# 05-Power.net
KiCad netlist of a schematic drawn in Altium Designer
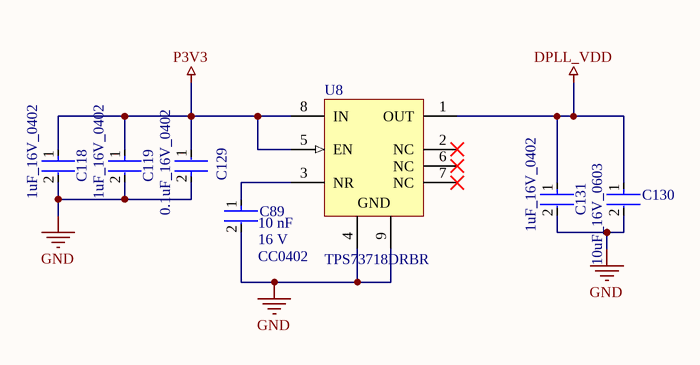
[diagram p0: 05-Power.SchDoc]

(export (version "E")
  (design (tool "Eeschema 10.0.6"))
  (components
    (comp (ref "C89")
      (value "10 nF")
      (footprint "FP-CC0402-MFG")
      (description "CAP CER 10000PF 16V X7R 0402")
      (fields
        (field (name "MANUFACTURER PART NUMBER") "CC0402KRX7R7BB103")
        (field (name "TOLERANCE") "0.1")
        (field (name "PACKAGE") "CC0402")
        (field (name "VOLTAGE RATING") "16 V")
      )
      (libsource (lib "Altium Content Vault") (part "11868f565c42a9108669ba33697ecf6"))
    )
    (comp (ref "C118")
      (value "1uF_16V_0402")
      (footprint "FP-0402-L_1_0_0_05-W_0_5-IPC_C")
      (description "None")
      (fields (field (name "TOLERANCE") "20%") (field (name "VOLTAGE") "16V"))
      (libsource (lib "Altium Content Vault") (part "b4654b650e69147ec39a6b967a45e02"))
    )
    (comp (ref "C119")
      (value "1uF_16V_0402")
      (footprint "FP-0402-L_1_0_0_05-W_0_5-IPC_C")
      (description "None")
      (fields (field (name "TOLERANCE") "20%") (field (name "VOLTAGE") "16V"))
      (libsource (lib "Altium Content Vault") (part "b4654b650e69147ec39a6b967a45e02"))
    )
    (comp (ref "C129")
      (value "0.1uF_16V_0402")
      (footprint "FP-GRM15-MFG")
      (description "CAP CER 0.1UF 16V X7R 0402")
      (fields (field (name "MANUFACTURER PART NUMBER") "GRM155R71C104KA88D") (field (name "TOLERANCE") "10%"))
      (libsource (lib "Altium Content Vault") (part "236180d848d6139a670b325ea6854c9"))
    )
    (comp (ref "C130")
      (value "10uF_16V_0603")
      (footprint "FP-MK107BA-IPC_A")
      (description "None")
      (fields (field (name "TOLERANCE") "20%"))
      (libsource (lib "Altium Content Vault") (part "b4654b650e69147ec39a6b967a45e02"))
    )
    (comp (ref "C131")
      (value "1uF_16V_0402")
      (footprint "FP-0402-L_1_0_0_05-W_0_5-IPC_C")
      (description "None")
      (fields (field (name "TOLERANCE") "20%") (field (name "VOLTAGE") "16V"))
      (libsource (lib "Altium Content Vault") (part "b4654b650e69147ec39a6b967a45e02"))
    )
    (comp (ref "U8")
      (value "TPS73718DRBR")
      (footprint "DRB0008A_V")
      (fields (field (name "MANUFACTURER") "Texas Instruments"))
      (libsource (lib "Altium Content Vault") (part "TI-TPS73718DRB8-1750X1500TP"))
    )
  )
  (nets
    (net (code "1") (name "DPLL_VDD") (class "Default")
      (node (ref "C130") (pin "1") (pinfunction "1_1") (pintype "passive"))
      (node (ref "C131") (pin "1") (pinfunction "1_1") (pintype "passive"))
      (node (ref "U8") (pin "1") (pinfunction "OUT_1") (pintype "power_in"))
    )
    (net (code "2") (name "GND") (class "Default")
      (node (ref "C118") (pin "2") (pinfunction "2_2") (pintype "passive"))
      (node (ref "C119") (pin "2") (pinfunction "2_2") (pintype "passive"))
      (node (ref "C129") (pin "2") (pinfunction "2_2") (pintype "passive"))
      (node (ref "C130") (pin "2") (pinfunction "2_2") (pintype "passive"))
      (node (ref "C131") (pin "2") (pinfunction "2_2") (pintype "passive"))
      (node (ref "C89") (pin "2") (pinfunction "2_2") (pintype "passive"))
      (node (ref "U8") (pin "4") (pinfunction "GND_4") (pintype "power_in"))
      (node (ref "U8") (pin "9") (pinfunction "GND_9") (pintype "power_in"))
    )
    (net (code "3") (name "Net-(U8-NR)") (class "Default")
      (node (ref "C89") (pin "1") (pinfunction "1_1") (pintype "passive"))
      (node (ref "U8") (pin "3") (pinfunction "NR_3") (pintype "passive"))
    )
    (net (code "4") (name "P3V3") (class "Default")
      (node (ref "C118") (pin "1") (pinfunction "1_1") (pintype "passive"))
      (node (ref "C119") (pin "1") (pinfunction "1_1") (pintype "passive"))
      (node (ref "C129") (pin "1") (pinfunction "1_1") (pintype "passive"))
      (node (ref "U8") (pin "5") (pinfunction "EN_5") (pintype "input"))
      (node (ref "U8") (pin "8") (pinfunction "IN_8") (pintype "power_in"))
    )
    (net (code "5") (name "unconnected-(U8-NC-Pad2)") (class "Default")
      (node (ref "U8") (pin "2") (pinfunction "NC_2") (pintype "passive+no_connect"))
    )
    (net (code "6") (name "unconnected-(U8-NC-Pad6)") (class "Default")
      (node (ref "U8") (pin "6") (pinfunction "NC_6") (pintype "passive+no_connect"))
    )
    (net (code "7") (name "unconnected-(U8-NC-Pad7)") (class "Default")
      (node (ref "U8") (pin "7") (pinfunction "NC_7") (pintype "passive+no_connect"))
    )
  )
)
